# Thermostat.net
KiCad netlist of a schematic drawn in EAGLE
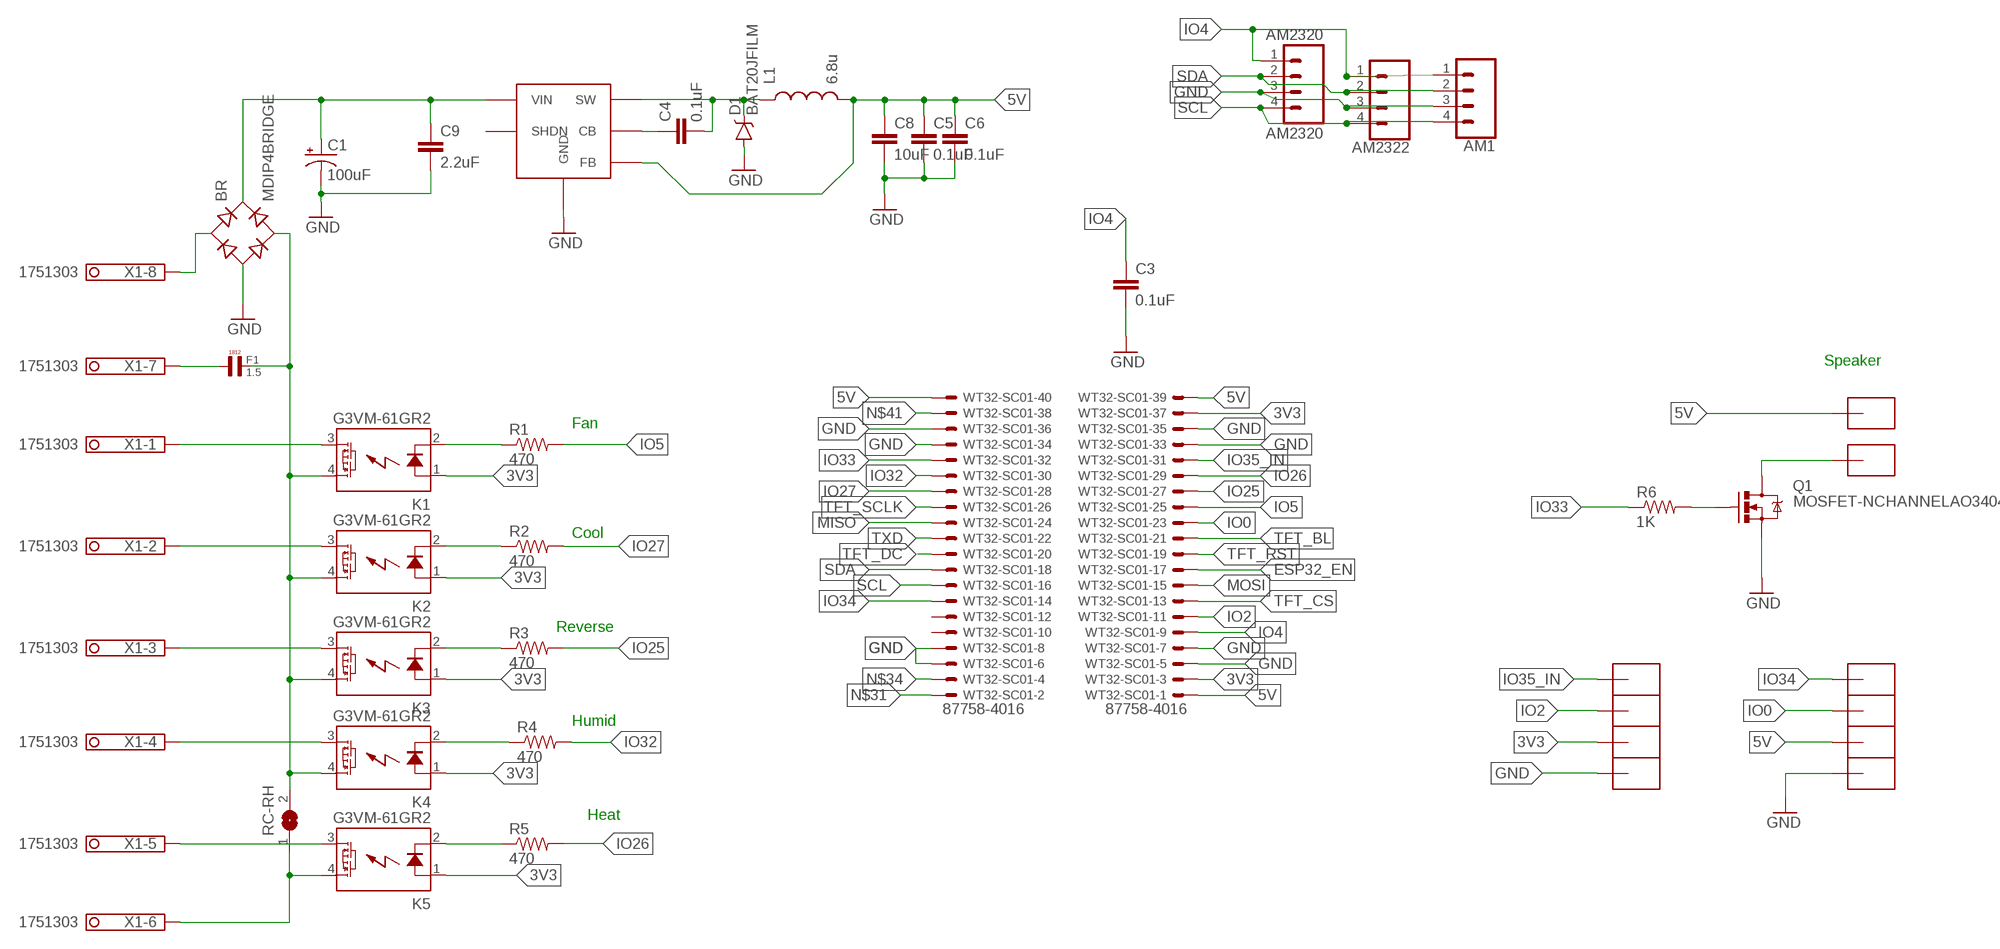
[diagram p0: schematic, sheet 1]

(export (version "E")
  (design (tool "Eeschema 10.0.6"))
  (components
    (comp (ref "AM1")
      (value "CONN_041.27MM")
      (footprint "eagle-import:1X04_1.27MM")
      (libsource (lib "eagle-import") (part "CONN_041.27MM"))
    )
    (comp (ref "AM2320")
      (value "AM2320")
      (footprint "eagle-import:1X04")
      (libsource (lib "eagle-import") (part "M04PTH"))
    )
    (comp (ref "AM2322")
      (value "CONN_041.27MM")
      (footprint "eagle-import:1X04_1.27MM")
      (libsource (lib "eagle-import") (part "CONN_041.27MM"))
    )
    (comp (ref "BR")
      (value "MDIP4BRIDGE")
      (footprint "eagle-import:MICRODIP4")
      (libsource (lib "eagle-import") (part "MDIP4BRIDGE"))
    )
    (comp (ref "C1")
      (value "100uF")
      (footprint "eagle-import:PANASONIC_C")
      (libsource (lib "eagle-import") (part "CAP_POLC"))
    )
    (comp (ref "C3")
      (value "0.1uF")
      (footprint "eagle-import:0805")
      (libsource (lib "eagle-import") (part "CAP0805"))
    )
    (comp (ref "C4")
      (value "0.1uF")
      (footprint "eagle-import:0805")
      (libsource (lib "eagle-import") (part "CAP0805"))
    )
    (comp (ref "C5")
      (value "0.1uF")
      (footprint "eagle-import:0805")
      (libsource (lib "eagle-import") (part "CAP0805"))
    )
    (comp (ref "C6")
      (value "0.1uF")
      (footprint "eagle-import:0805")
      (libsource (lib "eagle-import") (part "CAP0805"))
    )
    (comp (ref "C8")
      (value "10uF")
      (footprint "eagle-import:0805")
      (libsource (lib "eagle-import") (part "CAP0805"))
    )
    (comp (ref "C9")
      (value "2.2uF")
      (footprint "eagle-import:0805")
      (libsource (lib "eagle-import") (part "CAP0805"))
    )
    (comp (ref "D1")
      (value "BAT20JFILM")
      (footprint "eagle-import:SOD-323")
      (libsource (lib "eagle-import") (part "BAT20JFILM"))
    )
    (comp (ref "F1")
      (value "1.5")
      (footprint "eagle-import:L4,8")
      (libsource (lib "eagle-import") (part "0,1µF"))
    )
    (comp (ref "K1")
      (value "G3VM-61GR2")
      (footprint "eagle-import:SOP04")
      (libsource (lib "eagle-import") (part "AQYSOP22"))
    )
    (comp (ref "K2")
      (value "G3VM-61GR2")
      (footprint "eagle-import:SOP04")
      (libsource (lib "eagle-import") (part "AQYSOP22"))
    )
    (comp (ref "K3")
      (value "G3VM-61GR2")
      (footprint "eagle-import:SOP04")
      (libsource (lib "eagle-import") (part "AQYSOP22"))
    )
    (comp (ref "K4")
      (value "G3VM-61GR2")
      (footprint "eagle-import:SOP04")
      (libsource (lib "eagle-import") (part "AQYSOP22"))
    )
    (comp (ref "K5")
      (value "G3VM-61GR2")
      (footprint "eagle-import:SOP04")
      (libsource (lib "eagle-import") (part "AQYSOP22"))
    )
    (comp (ref "L1")
      (value "6.8u")
      (footprint "eagle-import:1007")
      (libsource (lib "eagle-import") (part "INDUCTOR1007"))
    )
    (comp (ref "Q1")
      (value "MOSFET-NCHANNELAO3404A")
      (footprint "eagle-import:SOT23-3")
      (libsource (lib "eagle-import") (part "MOSFET-NCHANNELAO3404A"))
    )
    (comp (ref "R1")
      (value "470")
      (footprint "eagle-import:0805")
      (libsource (lib "eagle-import") (part "RESISTOR0805-RES"))
    )
    (comp (ref "R2")
      (value "470")
      (footprint "eagle-import:0805")
      (libsource (lib "eagle-import") (part "RESISTOR0805-RES"))
    )
    (comp (ref "R3")
      (value "470")
      (footprint "eagle-import:0805")
      (libsource (lib "eagle-import") (part "RESISTOR0805-RES"))
    )
    (comp (ref "R4")
      (value "470")
      (footprint "eagle-import:0805")
      (libsource (lib "eagle-import") (part "RESISTOR0805-RES"))
    )
    (comp (ref "R5")
      (value "470")
      (footprint "eagle-import:0805")
      (libsource (lib "eagle-import") (part "RESISTOR0805-RES"))
    )
    (comp (ref "R6")
      (value "1K")
      (footprint "eagle-import:0805")
      (libsource (lib "eagle-import") (part "SparkFun-Resistors_RESISTOR0805-RES"))
    )
    (comp (ref "RC-RH")
      (value "SJ")
      (footprint "eagle-import:SJ")
      (libsource (lib "eagle-import") (part "SJ"))
    )
    (comp (ref "U$1")
      (value "SMD-PAD1SMD-PAD80X32")
      (footprint "eagle-import:SMD-PAD6")
      (libsource (lib "eagle-import") (part "SMD-PAD1SMD-PAD80X32"))
    )
    (comp (ref "U$2")
      (value "SMD-PAD1SMD-PAD80X32")
      (footprint "eagle-import:SMD-PAD6")
      (libsource (lib "eagle-import") (part "SMD-PAD1SMD-PAD80X32"))
    )
    (comp (ref "U$3")
      (value "SMD-PAD1SMD-PAD80X32")
      (footprint "eagle-import:SMD-PAD6")
      (libsource (lib "eagle-import") (part "SMD-PAD1SMD-PAD80X32"))
    )
    (comp (ref "U$4")
      (value "SMD-PAD1SMD-PAD80X32")
      (footprint "eagle-import:SMD-PAD6")
      (libsource (lib "eagle-import") (part "SMD-PAD1SMD-PAD80X32"))
    )
    (comp (ref "U$5")
      (value "SMD-PAD1SMD-PAD80X32")
      (footprint "eagle-import:SMD-PAD6")
      (libsource (lib "eagle-import") (part "SMD-PAD1SMD-PAD80X32"))
    )
    (comp (ref "U$6")
      (value "SMD-PAD1SMD-PAD80X32")
      (footprint "eagle-import:SMD-PAD6")
      (libsource (lib "eagle-import") (part "SMD-PAD1SMD-PAD80X32"))
    )
    (comp (ref "U$7")
      (value "SMD-PAD1SMD-PAD80X32")
      (footprint "eagle-import:SMD-PAD6")
      (libsource (lib "eagle-import") (part "SMD-PAD1SMD-PAD80X32"))
    )
    (comp (ref "U$9")
      (value "SMD-PAD1SMD-PAD80X32")
      (footprint "eagle-import:SMD-PAD6")
      (libsource (lib "eagle-import") (part "SMD-PAD1SMD-PAD80X32"))
    )
    (comp (ref "U$10")
      (value "SMD-PAD1SMD-PAD80X32")
      (footprint "eagle-import:SMD-PAD6")
      (libsource (lib "eagle-import") (part "SMD-PAD1SMD-PAD80X32"))
    )
    (comp (ref "U$11")
      (value "SMD-PAD1SMD-PAD80X32")
      (footprint "eagle-import:SMD-PAD6")
      (libsource (lib "eagle-import") (part "SMD-PAD1SMD-PAD80X32"))
    )
    (comp (ref "VREG")
      (value "LMR16006YQ")
      (footprint "eagle-import:SOT-23-6")
      (libsource (lib "eagle-import") (part "LMR16006YQ"))
    )
    (comp (ref "WT32-SC01")
      (value "87758-4016")
      (footprint "eagle-import:87758-4016")
      (fields (field (name "MF") "MOLEX"))
      (libsource (lib "eagle-import") (part "87758-4016"))
    )
    (comp (ref "X1")
      (value "1751303")
      (footprint "eagle-import:1751303")
      (libsource (lib "eagle-import") (part "1751303"))
    )
  )
  (nets
    (net (code "1") (name "3V3") (class "Default")
      (node (ref "K1") (pin "1") (pinfunction "A_1") (pintype "passive"))
      (node (ref "K2") (pin "1") (pinfunction "A_1") (pintype "passive"))
      (node (ref "K3") (pin "1") (pinfunction "A_1") (pintype "passive"))
      (node (ref "K4") (pin "1") (pinfunction "A_1") (pintype "passive"))
      (node (ref "K5") (pin "1") (pinfunction "A_1") (pintype "passive"))
      (node (ref "U$1") (pin ">PAD") (pinfunction "P$1_>PAD") (pintype "bidirectional"))
      (node (ref "WT32-SC01") (pin "3") (pinfunction "S_3") (pintype "passive"))
      (node (ref "WT32-SC01") (pin "37") (pinfunction "S_37") (pintype "passive"))
    )
    (net (code "2") (name "5V") (class "Default")
      (node (ref "C5") (pin "1") (pinfunction "1_1") (pintype "passive"))
      (node (ref "C6") (pin "1") (pinfunction "1_1") (pintype "passive"))
      (node (ref "C8") (pin "1") (pinfunction "1_1") (pintype "passive"))
      (node (ref "L1") (pin "2") (pinfunction "2_2") (pintype "passive"))
      (node (ref "U$5") (pin ">PAD") (pinfunction "P$1_>PAD") (pintype "bidirectional"))
      (node (ref "U$7") (pin ">PAD") (pinfunction "P$1_>PAD") (pintype "bidirectional"))
      (node (ref "VREG") (pin "3") (pinfunction "FB_3") (pintype "input"))
      (node (ref "WT32-SC01") (pin "1") (pinfunction "S_1") (pintype "passive"))
      (node (ref "WT32-SC01") (pin "39") (pinfunction "S_39") (pintype "passive"))
      (node (ref "WT32-SC01") (pin "40") (pinfunction "S_40") (pintype "passive"))
    )
    (net (code "3") (name "ESP32_EN") (class "Default")
      (node (ref "WT32-SC01") (pin "17") (pinfunction "S_17") (pintype "passive"))
    )
    (net (code "4") (name "GND") (class "Default")
      (node (ref "AM1") (pin "3") (pinfunction "3_3") (pintype "passive"))
      (node (ref "AM2320") (pin "3") (pinfunction "3_3") (pintype "passive"))
      (node (ref "AM2322") (pin "3") (pinfunction "3_3") (pintype "passive"))
      (node (ref "BR") (pin "-") (pinfunction "-_-") (pintype "passive"))
      (node (ref "C1") (pin "-") (pinfunction "-_-") (pintype "passive"))
      (node (ref "C3") (pin "2") (pinfunction "2_2") (pintype "passive"))
      (node (ref "C5") (pin "2") (pinfunction "2_2") (pintype "passive"))
      (node (ref "C6") (pin "2") (pinfunction "2_2") (pintype "passive"))
      (node (ref "C8") (pin "2") (pinfunction "2_2") (pintype "passive"))
      (node (ref "C9") (pin "2") (pinfunction "2_2") (pintype "passive"))
      (node (ref "D1") (pin "A") (pinfunction "A_A") (pintype "passive"))
      (node (ref "Q1") (pin "2") (pinfunction "S_2") (pintype "passive"))
      (node (ref "U$2") (pin ">PAD") (pinfunction "P$1_>PAD") (pintype "bidirectional"))
      (node (ref "U$9") (pin ">PAD") (pinfunction "P$1_>PAD") (pintype "bidirectional"))
      (node (ref "VREG") (pin "2") (pinfunction "GND_2") (pintype "input"))
      (node (ref "WT32-SC01") (pin "33") (pinfunction "S_33") (pintype "passive"))
      (node (ref "WT32-SC01") (pin "34") (pinfunction "S_34") (pintype "passive"))
      (node (ref "WT32-SC01") (pin "35") (pinfunction "S_35") (pintype "passive"))
      (node (ref "WT32-SC01") (pin "36") (pinfunction "S_36") (pintype "passive"))
      (node (ref "WT32-SC01") (pin "5") (pinfunction "S_5") (pintype "passive"))
      (node (ref "WT32-SC01") (pin "6") (pinfunction "S_6") (pintype "passive"))
      (node (ref "WT32-SC01") (pin "7") (pinfunction "S_7") (pintype "passive"))
      (node (ref "WT32-SC01") (pin "8") (pinfunction "S_8") (pintype "passive"))
    )
    (net (code "5") (name "IO0") (class "Default")
      (node (ref "U$10") (pin ">PAD") (pinfunction "P$1_>PAD") (pintype "bidirectional"))
      (node (ref "WT32-SC01") (pin "23") (pinfunction "S_23") (pintype "passive"))
    )
    (net (code "6") (name "IO2") (class "Default")
      (node (ref "U$3") (pin ">PAD") (pinfunction "P$1_>PAD") (pintype "bidirectional"))
      (node (ref "WT32-SC01") (pin "11") (pinfunction "S_11") (pintype "passive"))
    )
    (net (code "7") (name "IO4") (class "Default")
      (node (ref "AM1") (pin "1") (pinfunction "1_1") (pintype "passive"))
      (node (ref "AM2320") (pin "1") (pinfunction "1_1") (pintype "passive"))
      (node (ref "AM2322") (pin "1") (pinfunction "1_1") (pintype "passive"))
      (node (ref "C3") (pin "1") (pinfunction "1_1") (pintype "passive"))
      (node (ref "WT32-SC01") (pin "9") (pinfunction "S_9") (pintype "passive"))
    )
    (net (code "8") (name "IO5") (class "Default")
      (node (ref "R1") (pin "2") (pinfunction "2_2") (pintype "passive"))
      (node (ref "WT32-SC01") (pin "25") (pinfunction "S_25") (pintype "passive"))
    )
    (net (code "9") (name "IO25") (class "Default")
      (node (ref "R3") (pin "2") (pinfunction "2_2") (pintype "passive"))
      (node (ref "WT32-SC01") (pin "27") (pinfunction "S_27") (pintype "passive"))
    )
    (net (code "10") (name "IO26") (class "Default")
      (node (ref "R5") (pin "2") (pinfunction "2_2") (pintype "passive"))
      (node (ref "WT32-SC01") (pin "29") (pinfunction "S_29") (pintype "passive"))
    )
    (net (code "11") (name "IO27") (class "Default")
      (node (ref "R2") (pin "2") (pinfunction "2_2") (pintype "passive"))
      (node (ref "WT32-SC01") (pin "28") (pinfunction "S_28") (pintype "passive"))
    )
    (net (code "12") (name "IO32") (class "Default")
      (node (ref "R4") (pin "2") (pinfunction "2_2") (pintype "passive"))
      (node (ref "WT32-SC01") (pin "30") (pinfunction "S_30") (pintype "passive"))
    )
    (net (code "13") (name "IO33") (class "Default")
      (node (ref "R6") (pin "1") (pinfunction "1_1") (pintype "passive"))
      (node (ref "WT32-SC01") (pin "32") (pinfunction "S_32") (pintype "passive"))
    )
    (net (code "14") (name "IO34") (class "Default")
      (node (ref "U$6") (pin ">PAD") (pinfunction "P$1_>PAD") (pintype "bidirectional"))
      (node (ref "WT32-SC01") (pin "14") (pinfunction "S_14") (pintype "passive"))
    )
    (net (code "15") (name "IO35_IN") (class "Default")
      (node (ref "U$4") (pin ">PAD") (pinfunction "P$1_>PAD") (pintype "bidirectional"))
      (node (ref "WT32-SC01") (pin "31") (pinfunction "S_31") (pintype "passive"))
    )
    (net (code "16") (name "MISO") (class "Default")
      (node (ref "WT32-SC01") (pin "24") (pinfunction "S_24") (pintype "passive"))
    )
    (net (code "17") (name "MOSI") (class "Default")
      (node (ref "WT32-SC01") (pin "15") (pinfunction "S_15") (pintype "passive"))
    )
    (net (code "18") (name "N$31") (class "Default")
      (node (ref "WT32-SC01") (pin "2") (pinfunction "S_2") (pintype "passive"))
    )
    (net (code "19") (name "N$34") (class "Default")
      (node (ref "WT32-SC01") (pin "4") (pinfunction "S_4") (pintype "passive"))
    )
    (net (code "20") (name "N$41") (class "Default")
      (node (ref "WT32-SC01") (pin "38") (pinfunction "S_38") (pintype "passive"))
    )
    (net (code "21") (name "Net-(F1-1)") (class "Default")
      (node (ref "F1") (pin "P$1") (pinfunction "1_P$1") (pintype "passive"))
      (node (ref "X1") (pin "7") (pinfunction "K_7") (pintype "passive"))
    )
    (net (code "22") (name "Net-(F1-2)") (class "Default")
      (node (ref "BR") (pin "AC2") (pinfunction "AC2_AC2") (pintype "passive"))
      (node (ref "F1") (pin "P$2") (pinfunction "2_P$2") (pintype "passive"))
      (node (ref "K1") (pin "4") (pinfunction "DS1_4") (pintype "passive"))
      (node (ref "K2") (pin "4") (pinfunction "DS1_4") (pintype "passive"))
      (node (ref "K3") (pin "4") (pinfunction "DS1_4") (pintype "passive"))
      (node (ref "K4") (pin "4") (pinfunction "DS1_4") (pintype "passive"))
      (node (ref "RC-RH") (pin "2") (pinfunction "2_2") (pintype "passive"))
    )
    (net (code "23") (name "Net-(K1-DS2)") (class "Default")
      (node (ref "K1") (pin "3") (pinfunction "DS2_3") (pintype "passive"))
      (node (ref "X1") (pin "1") (pinfunction "K_1") (pintype "passive"))
    )
    (net (code "24") (name "Net-(K1-K)") (class "Default")
      (node (ref "K1") (pin "2") (pinfunction "K_2") (pintype "passive"))
      (node (ref "R1") (pin "1") (pinfunction "1_1") (pintype "passive"))
    )
    (net (code "25") (name "Net-(K2-DS2)") (class "Default")
      (node (ref "K2") (pin "3") (pinfunction "DS2_3") (pintype "passive"))
      (node (ref "X1") (pin "2") (pinfunction "K_2") (pintype "passive"))
    )
    (net (code "26") (name "Net-(K2-K)") (class "Default")
      (node (ref "K2") (pin "2") (pinfunction "K_2") (pintype "passive"))
      (node (ref "R2") (pin "1") (pinfunction "1_1") (pintype "passive"))
    )
    (net (code "27") (name "Net-(K3-DS2)") (class "Default")
      (node (ref "K3") (pin "3") (pinfunction "DS2_3") (pintype "passive"))
      (node (ref "X1") (pin "3") (pinfunction "K_3") (pintype "passive"))
    )
    (net (code "28") (name "Net-(K3-K)") (class "Default")
      (node (ref "K3") (pin "2") (pinfunction "K_2") (pintype "passive"))
      (node (ref "R3") (pin "1") (pinfunction "1_1") (pintype "passive"))
    )
    (net (code "29") (name "Net-(K4-DS2)") (class "Default")
      (node (ref "K4") (pin "3") (pinfunction "DS2_3") (pintype "passive"))
      (node (ref "X1") (pin "4") (pinfunction "K_4") (pintype "passive"))
    )
    (net (code "30") (name "Net-(K4-K)") (class "Default")
      (node (ref "K4") (pin "2") (pinfunction "K_2") (pintype "passive"))
      (node (ref "R4") (pin "1") (pinfunction "1_1") (pintype "passive"))
    )
    (net (code "31") (name "Net-(K5-DS1)") (class "Default")
      (node (ref "K5") (pin "4") (pinfunction "DS1_4") (pintype "passive"))
      (node (ref "RC-RH") (pin "1") (pinfunction "1_1") (pintype "passive"))
      (node (ref "X1") (pin "6") (pinfunction "K_6") (pintype "passive"))
    )
    (net (code "32") (name "Net-(K5-DS2)") (class "Default")
      (node (ref "K5") (pin "3") (pinfunction "DS2_3") (pintype "passive"))
      (node (ref "X1") (pin "5") (pinfunction "K_5") (pintype "passive"))
    )
    (net (code "33") (name "Net-(K5-K)") (class "Default")
      (node (ref "K5") (pin "2") (pinfunction "K_2") (pintype "passive"))
      (node (ref "R5") (pin "1") (pinfunction "1_1") (pintype "passive"))
    )
    (net (code "34") (name "Net-(Q1-D)") (class "Default")
      (node (ref "Q1") (pin "3") (pinfunction "D_3") (pintype "passive"))
      (node (ref "U$11") (pin ">PAD") (pinfunction "P$1_>PAD") (pintype "bidirectional"))
    )
    (net (code "35") (name "Net-(Q1-G)") (class "Default")
      (node (ref "Q1") (pin "1") (pinfunction "G_1") (pintype "passive"))
      (node (ref "R6") (pin "2") (pinfunction "2_2") (pintype "passive"))
    )
    (net (code "36") (name "Net-(VREG-CB)") (class "Default")
      (node (ref "C4") (pin "1") (pinfunction "1_1") (pintype "passive"))
      (node (ref "VREG") (pin "1") (pinfunction "CB_1") (pintype "input"))
    )
    (net (code "37") (name "Net-(VREG-SW)") (class "Default")
      (node (ref "C4") (pin "2") (pinfunction "2_2") (pintype "passive"))
      (node (ref "D1") (pin "C") (pinfunction "C_C") (pintype "passive"))
      (node (ref "L1") (pin "1") (pinfunction "1_1") (pintype "passive"))
      (node (ref "VREG") (pin "6") (pinfunction "SW_6") (pintype "output"))
    )
    (net (code "38") (name "Net-(VREG-VIN)") (class "Default")
      (node (ref "BR") (pin "+") (pinfunction "+_+") (pintype "passive"))
      (node (ref "C1") (pin "+") (pinfunction "+_+") (pintype "passive"))
      (node (ref "C9") (pin "1") (pinfunction "1_1") (pintype "passive"))
      (node (ref "VREG") (pin "5") (pinfunction "VIN_5") (pintype "input"))
    )
    (net (code "39") (name "Net-(X1H-K)") (class "Default")
      (node (ref "BR") (pin "AC1") (pinfunction "AC1_AC1") (pintype "passive"))
      (node (ref "X1") (pin "8") (pinfunction "K_8") (pintype "passive"))
    )
    (net (code "40") (name "SCL") (class "Default")
      (node (ref "AM1") (pin "4") (pinfunction "4_4") (pintype "passive"))
      (node (ref "AM2320") (pin "4") (pinfunction "4_4") (pintype "passive"))
      (node (ref "AM2322") (pin "4") (pinfunction "4_4") (pintype "passive"))
      (node (ref "WT32-SC01") (pin "16") (pinfunction "S_16") (pintype "passive"))
    )
    (net (code "41") (name "SDA") (class "Default")
      (node (ref "AM1") (pin "2") (pinfunction "2_2") (pintype "passive"))
      (node (ref "AM2320") (pin "2") (pinfunction "2_2") (pintype "passive"))
      (node (ref "AM2322") (pin "2") (pinfunction "2_2") (pintype "passive"))
      (node (ref "WT32-SC01") (pin "18") (pinfunction "S_18") (pintype "passive"))
    )
    (net (code "42") (name "TFT_BL") (class "Default")
      (node (ref "WT32-SC01") (pin "21") (pinfunction "S_21") (pintype "passive"))
    )
    (net (code "43") (name "TFT_CS") (class "Default")
      (node (ref "WT32-SC01") (pin "13") (pinfunction "S_13") (pintype "passive"))
    )
    (net (code "44") (name "TFT_DC") (class "Default")
      (node (ref "WT32-SC01") (pin "20") (pinfunction "S_20") (pintype "passive"))
    )
    (net (code "45") (name "TFT_RST") (class "Default")
      (node (ref "WT32-SC01") (pin "19") (pinfunction "S_19") (pintype "passive"))
    )
    (net (code "46") (name "TFT_SCLK") (class "Default")
      (node (ref "WT32-SC01") (pin "26") (pinfunction "S_26") (pintype "passive"))
    )
    (net (code "47") (name "TXD") (class "Default")
      (node (ref "WT32-SC01") (pin "22") (pinfunction "S_22") (pintype "passive"))
    )
    (net (code "48") (name "unconnected-(VREG-SHDN-Pad4)") (class "Default")
      (node (ref "VREG") (pin "4") (pinfunction "SHDN_4") (pintype "input"))
    )
    (net (code "49") (name "unconnected-(WT32-SC01B-S-Pad10)") (class "Default")
      (node (ref "WT32-SC01") (pin "10") (pinfunction "S_10") (pintype "passive"))
    )
    (net (code "50") (name "unconnected-(WT32-SC01D-S-Pad12)") (class "Default")
      (node (ref "WT32-SC01") (pin "12") (pinfunction "S_12") (pintype "passive"))
    )
  )
)
